# 6_CH340C.net
KiCad netlist of a schematic drawn in Altium Designer
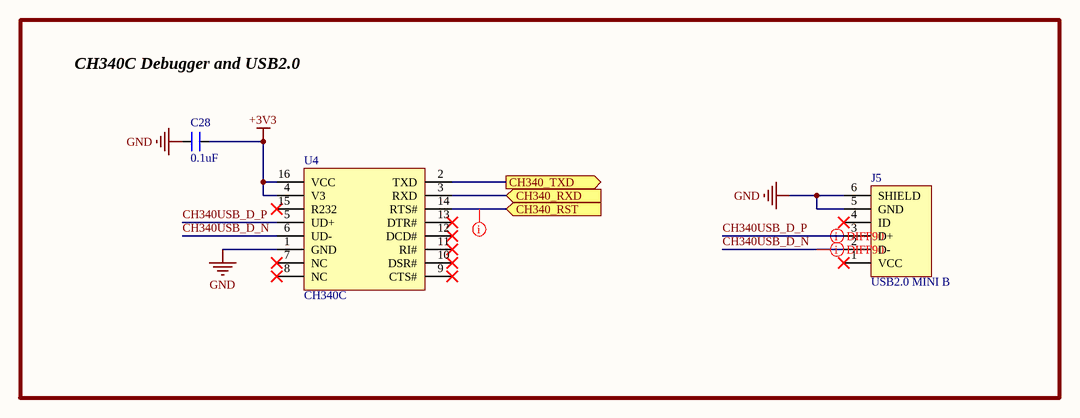
[diagram p0: [6] CH340C.SchDoc]

(export (version "E")
  (design (tool "Eeschema 10.0.6"))
  (components
    (comp (ref "C28")
      (value "0.1uF")
      (footprint "CAP_0805")
      (description "0.1µF ±10% 50V Ceramic Capacitor X7R 0805 (2012 Metric)")
      (fields
        (field (name "MANUFACTURER") "Samsung")
        (field (name "MANUFACTURER PART NUMBER") "CL21B104KBCNNNC")
      )
      (libsource (lib "ESTEEMPCBLIB") (part "CAP_0.1uF-50V-10%-0805"))
    )
    (comp (ref "J5")
      (value "USB2.0 MINI B")
      (footprint "CON_690-005-299-043")
      (description "USB - mini B USB 2.0 Receptacle Connector 5 Position Surface Mount, Right Angle")
      (fields
        (field (name "MANUFACTURER") "EDAC")
        (field (name "MANUFACTURER PART NUMBER") "690-005-299-043")
      )
      (libsource (lib "ESTEEMPCBLIB") (part "CON_USB2.0-MINIB-SMD"))
    )
    (comp (ref "U4")
      (value "CH340C")
      (footprint "SOIC16_50_284_25X90_SMT")
      (description "USB Bridge, USB to UART USB 2.0 UART Interface")
      (fields (field (name "MANUFACTURER") "Olimex"))
      (libsource (lib "ESTEEMPCBLIB") (part "IC_CH340C"))
    )
  )
  (nets
    (net (code "1") (name "+3V3") (class "Default")
      (node (ref "C28") (pin "2") (pinfunction "2_2") (pintype "passive"))
      (node (ref "U4") (pin "16") (pinfunction "VCC_16") (pintype "passive"))
      (node (ref "U4") (pin "4") (pinfunction "V3_4") (pintype "passive"))
    )
    (net (code "2") (name "/CH340USB_D_N") (class "Default")
      (node (ref "J5") (pin "2") (pinfunction "D-_2") (pintype "passive"))
      (node (ref "U4") (pin "6") (pinfunction "UD-_6") (pintype "passive"))
    )
    (net (code "3") (name "/CH340USB_D_P") (class "Default")
      (node (ref "J5") (pin "3") (pinfunction "D+_3") (pintype "passive"))
      (node (ref "U4") (pin "5") (pinfunction "UD+_5") (pintype "passive"))
    )
    (net (code "4") (name "/CH340_RST") (class "Default")
      (node (ref "U4") (pin "14") (pinfunction "RTS#_14") (pintype "passive"))
    )
    (net (code "5") (name "/CH340_RXD") (class "Default")
      (node (ref "U4") (pin "3") (pinfunction "RXD_3") (pintype "passive"))
    )
    (net (code "6") (name "/CH340_TXD") (class "Default")
      (node (ref "U4") (pin "2") (pinfunction "TXD_2") (pintype "passive"))
    )
    (net (code "7") (name "GND") (class "Default")
      (node (ref "C28") (pin "1") (pinfunction "1_1") (pintype "passive"))
      (node (ref "J5") (pin "5") (pinfunction "GND_5") (pintype "passive"))
      (node (ref "J5") (pin "6") (pinfunction "SHIELD_6") (pintype "passive"))
      (node (ref "U4") (pin "1") (pinfunction "GND_1") (pintype "passive"))
    )
    (net (code "8") (name "unconnected-(J5-ID-Pad4)") (class "Default")
      (node (ref "J5") (pin "4") (pinfunction "ID_4") (pintype "passive+no_connect"))
    )
    (net (code "9") (name "unconnected-(J5-VCC-Pad1)") (class "Default")
      (node (ref "J5") (pin "1") (pinfunction "VCC_1") (pintype "passive+no_connect"))
    )
    (net (code "10") (name "unconnected-(U4-CTS#-Pad9)") (class "Default")
      (node (ref "U4") (pin "9") (pinfunction "CTS#_9") (pintype "passive+no_connect"))
    )
    (net (code "11") (name "unconnected-(U4-DCD#-Pad12)") (class "Default")
      (node (ref "U4") (pin "12") (pinfunction "DCD#_12") (pintype "passive+no_connect"))
    )
    (net (code "12") (name "unconnected-(U4-DSR#-Pad10)") (class "Default")
      (node (ref "U4") (pin "10") (pinfunction "DSR#_10") (pintype "passive+no_connect"))
    )
    (net (code "13") (name "unconnected-(U4-DTR#-Pad13)") (class "Default")
      (node (ref "U4") (pin "13") (pinfunction "DTR#_13") (pintype "passive+no_connect"))
    )
    (net (code "14") (name "unconnected-(U4-NC-Pad7)") (class "Default")
      (node (ref "U4") (pin "7") (pinfunction "NC_7") (pintype "passive+no_connect"))
    )
    (net (code "15") (name "unconnected-(U4-NC-Pad8)") (class "Default")
      (node (ref "U4") (pin "8") (pinfunction "NC_8") (pintype "passive+no_connect"))
    )
    (net (code "16") (name "unconnected-(U4-R232-Pad15)") (class "Default")
      (node (ref "U4") (pin "15") (pinfunction "R232_15") (pintype "passive+no_connect"))
    )
    (net (code "17") (name "unconnected-(U4-RI#-Pad11)") (class "Default")
      (node (ref "U4") (pin "11") (pinfunction "RI#_11") (pintype "passive+no_connect"))
    )
  )
)
